# SCH_dock_2024-07-09.net
KiCad netlist of a schematic drawn in EasyEDA
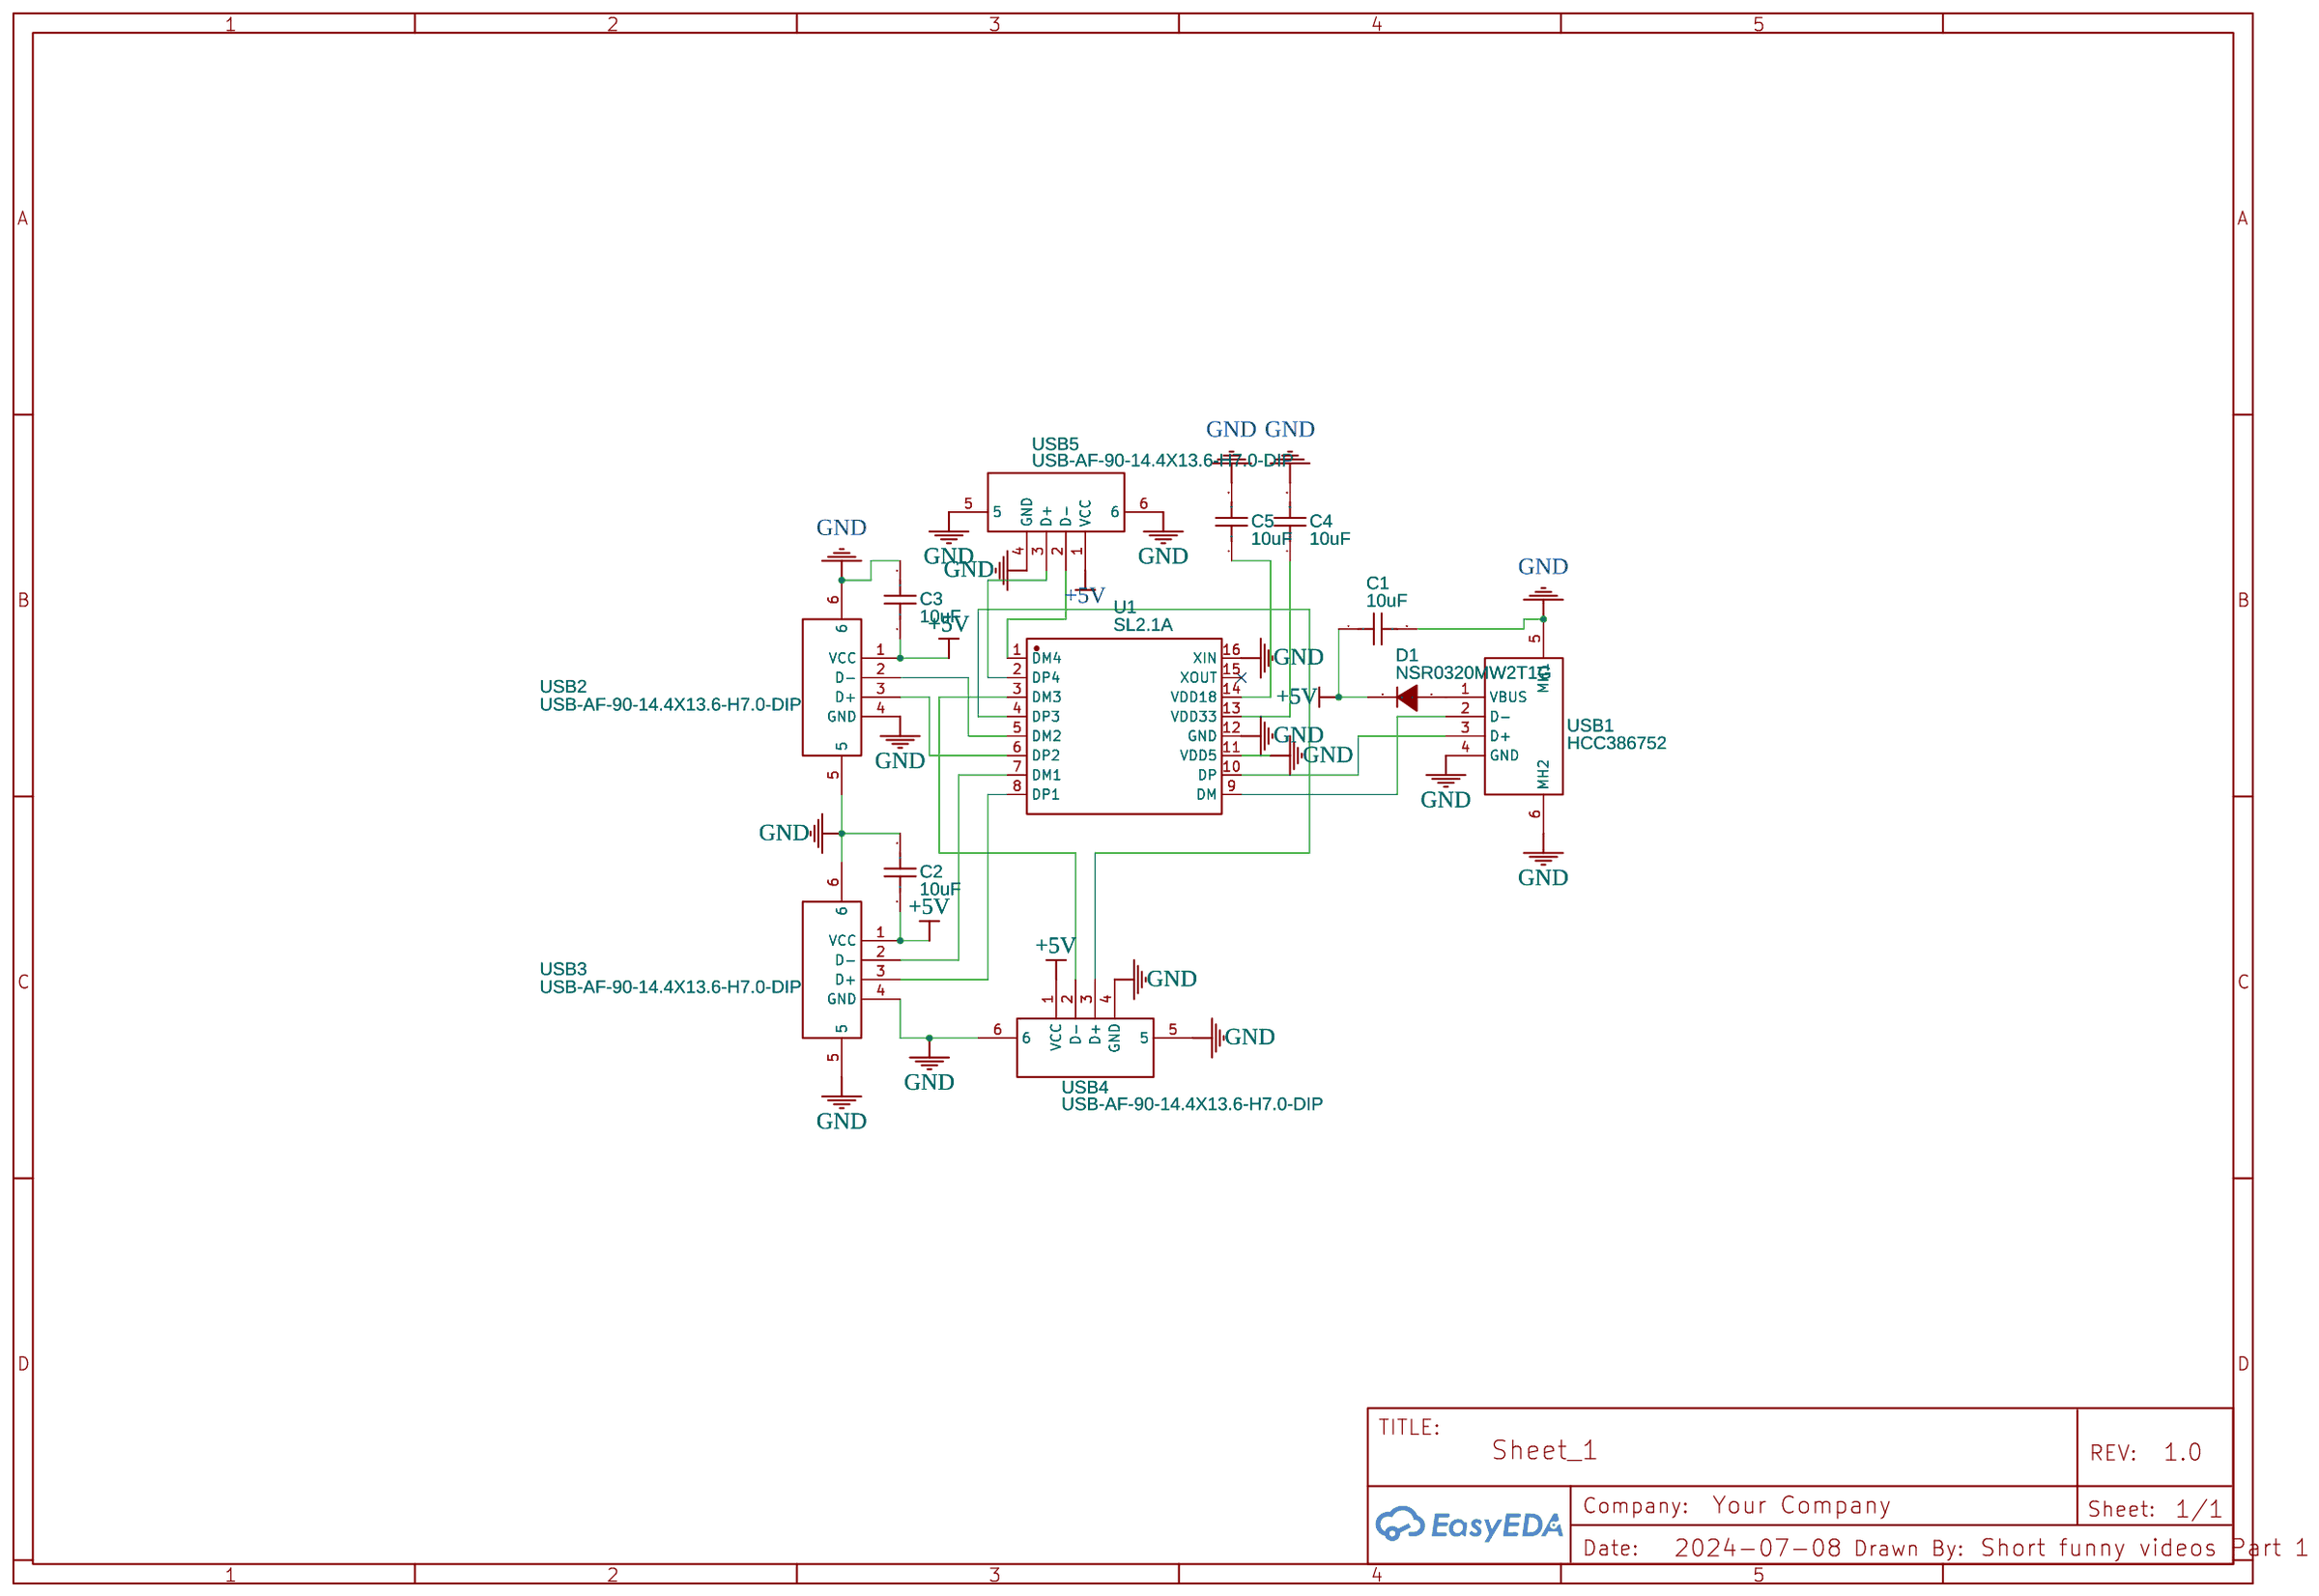
[diagram p0: schematic sheet]

(export (version "E")
  (design (tool "Eeschema 10.0.6"))
  (components
    (comp (ref "C1")
      (value "10uF")
      (fields
        (field (name "Manufacturer Part") "CL10A106KP8NNNC")
        (field (name "Manufacturer") "SAMSUNG(三星)")
      )
      (libsource (lib "") (part "CL10A106KP8NNNC_2"))
    )
    (comp (ref "C2")
      (value "10uF")
      (fields
        (field (name "Manufacturer Part") "CL10A106KP8NNNC")
        (field (name "Manufacturer") "SAMSUNG(三星)")
      )
      (libsource (lib "") (part "CL10A106KP8NNNC_1"))
    )
    (comp (ref "C3")
      (value "10uF")
      (fields
        (field (name "Manufacturer Part") "CL10A106KP8NNNC")
        (field (name "Manufacturer") "SAMSUNG(三星)")
      )
      (libsource (lib "") (part "CL10A106KP8NNNC"))
    )
    (comp (ref "C4")
      (value "10uF")
      (fields
        (field (name "Manufacturer Part") "CL10A106KP8NNNC")
        (field (name "Manufacturer") "SAMSUNG(三星)")
      )
      (libsource (lib "") (part "CL10A106KP8NNNC"))
    )
    (comp (ref "C5")
      (value "10uF")
      (fields
        (field (name "Manufacturer Part") "CL10A106KP8NNNC")
        (field (name "Manufacturer") "SAMSUNG(三星)")
      )
      (libsource (lib "") (part "CL10A106KP8NNNC"))
    )
    (comp (ref "D1")
      (value "NSR0320MW2T1G")
      (fields (field (name "Manufacturer") "onsemi(安森美)"))
      (libsource (lib "") (part "NSR0320MW2T1G"))
    )
    (comp (ref "U1")
      (value "SL2.1A")
      (fields (field (name "Manufacturer") "CoreChips(和芯润德)"))
      (libsource (lib "") (part "SL2.1A"))
    )
    (comp (ref "USB1")
      (value "HCC386752")
      (fields (field (name "Manufacturer Part") "U-USBAR04P-M003") (field (name "Manufacturer") "Ckmtw(灿科盟)"))
      (libsource (lib "") (part "HCC386752"))
    )
    (comp (ref "USB2")
      (value "USB-AF-90-14.4X13.6-H7.0-DIP")
      (fields (field (name "Manufacturer Part") "903-131A1011D10100") (field (name "Manufacturer") "精拓金"))
      (libsource (lib "") (part "USB-AF-90-14.4X13.6-H7.0-DIP"))
    )
    (comp (ref "USB3")
      (value "USB-AF-90-14.4X13.6-H7.0-DIP")
      (fields (field (name "Manufacturer Part") "903-131A1011D10100") (field (name "Manufacturer") "精拓金"))
      (libsource (lib "") (part "USB-AF-90-14.4X13.6-H7.0-DIP"))
    )
    (comp (ref "USB4")
      (value "USB-AF-90-14.4X13.6-H7.0-DIP")
      (fields (field (name "Manufacturer Part") "903-131A1011D10100") (field (name "Manufacturer") "精拓金"))
      (libsource (lib "") (part "USB-AF-90-14.4X13.6-H7.0-DIP_2"))
    )
    (comp (ref "USB5")
      (value "USB-AF-90-14.4X13.6-H7.0-DIP")
      (fields (field (name "Manufacturer Part") "903-131A1011D10100") (field (name "Manufacturer") "精拓金"))
      (libsource (lib "") (part "USB-AF-90-14.4X13.6-H7.0-DIP_1"))
    )
  )
  (nets
    (net (code "1") (name "+5V") (class "Default")
      (node (ref "C1") (pin "1") (pinfunction "1_1") (pintype "unspecified"))
      (node (ref "C2") (pin "2") (pinfunction "2_2") (pintype "unspecified"))
      (node (ref "C3") (pin "1") (pinfunction "1_1") (pintype "unspecified"))
      (node (ref "D1") (pin "1") (pinfunction "C_1") (pintype "unspecified"))
      (node (ref "USB2") (pin "1") (pinfunction "VCC_1") (pintype "unspecified"))
      (node (ref "USB3") (pin "1") (pinfunction "VCC_1") (pintype "unspecified"))
      (node (ref "USB4") (pin "1") (pinfunction "VCC_1") (pintype "unspecified"))
      (node (ref "USB5") (pin "1") (pinfunction "VCC_1") (pintype "unspecified"))
    )
    (net (code "2") (name "GND") (class "Default")
      (node (ref "C1") (pin "2") (pinfunction "2_2") (pintype "unspecified"))
      (node (ref "C2") (pin "1") (pinfunction "1_1") (pintype "unspecified"))
      (node (ref "C3") (pin "2") (pinfunction "2_2") (pintype "unspecified"))
      (node (ref "C4") (pin "2") (pinfunction "2_2") (pintype "unspecified"))
      (node (ref "C5") (pin "2") (pinfunction "2_2") (pintype "unspecified"))
      (node (ref "U1") (pin "11") (pinfunction "VDD5_11") (pintype "unspecified"))
      (node (ref "U1") (pin "12") (pinfunction "GND_12") (pintype "unspecified"))
      (node (ref "U1") (pin "16") (pinfunction "XIN_16") (pintype "unspecified"))
      (node (ref "USB1") (pin "4") (pinfunction "GND_4") (pintype "unspecified"))
      (node (ref "USB1") (pin "5") (pinfunction "MH1_5") (pintype "unspecified"))
      (node (ref "USB1") (pin "6") (pinfunction "MH2_6") (pintype "unspecified"))
      (node (ref "USB2") (pin "4") (pinfunction "GND_4") (pintype "unspecified"))
      (node (ref "USB2") (pin "5") (pinfunction "5_5") (pintype "unspecified"))
      (node (ref "USB2") (pin "6") (pinfunction "6_6") (pintype "unspecified"))
      (node (ref "USB3") (pin "4") (pinfunction "GND_4") (pintype "unspecified"))
      (node (ref "USB3") (pin "5") (pinfunction "5_5") (pintype "unspecified"))
      (node (ref "USB3") (pin "6") (pinfunction "6_6") (pintype "unspecified"))
      (node (ref "USB4") (pin "4") (pinfunction "GND_4") (pintype "unspecified"))
      (node (ref "USB4") (pin "5") (pinfunction "5_5") (pintype "unspecified"))
      (node (ref "USB4") (pin "6") (pinfunction "6_6") (pintype "unspecified"))
      (node (ref "USB5") (pin "4") (pinfunction "GND_4") (pintype "unspecified"))
      (node (ref "USB5") (pin "5") (pinfunction "5_5") (pintype "unspecified"))
      (node (ref "USB5") (pin "6") (pinfunction "6_6") (pintype "unspecified"))
    )
    (net (code "3") (name "Net-(D1-A)") (class "Default")
      (node (ref "D1") (pin "2") (pinfunction "A_2") (pintype "unspecified"))
      (node (ref "USB1") (pin "1") (pinfunction "VBUS_1") (pintype "unspecified"))
    )
    (net (code "4") (name "Net-(U1-DM)") (class "Default")
      (node (ref "U1") (pin "9") (pinfunction "DM_9") (pintype "unspecified"))
      (node (ref "USB1") (pin "2") (pinfunction "D-_2") (pintype "unspecified"))
    )
    (net (code "5") (name "Net-(U1-DM1)") (class "Default")
      (node (ref "U1") (pin "7") (pinfunction "DM1_7") (pintype "unspecified"))
      (node (ref "USB3") (pin "2") (pinfunction "D-_2") (pintype "unspecified"))
    )
    (net (code "6") (name "Net-(U1-DM2)") (class "Default")
      (node (ref "U1") (pin "5") (pinfunction "DM2_5") (pintype "unspecified"))
      (node (ref "USB2") (pin "2") (pinfunction "D-_2") (pintype "unspecified"))
    )
    (net (code "7") (name "Net-(U1-DM3)") (class "Default")
      (node (ref "U1") (pin "3") (pinfunction "DM3_3") (pintype "unspecified"))
      (node (ref "USB4") (pin "2") (pinfunction "D-_2") (pintype "unspecified"))
    )
    (net (code "8") (name "Net-(U1-DM4)") (class "Default")
      (node (ref "U1") (pin "1") (pinfunction "DM4_1") (pintype "unspecified"))
      (node (ref "USB5") (pin "2") (pinfunction "D-_2") (pintype "unspecified"))
    )
    (net (code "9") (name "Net-(U1-DP)") (class "Default")
      (node (ref "U1") (pin "10") (pinfunction "DP_10") (pintype "unspecified"))
      (node (ref "USB1") (pin "3") (pinfunction "D+_3") (pintype "unspecified"))
    )
    (net (code "10") (name "Net-(U1-DP1)") (class "Default")
      (node (ref "U1") (pin "8") (pinfunction "DP1_8") (pintype "unspecified"))
      (node (ref "USB3") (pin "3") (pinfunction "D+_3") (pintype "unspecified"))
    )
    (net (code "11") (name "Net-(U1-DP2)") (class "Default")
      (node (ref "U1") (pin "6") (pinfunction "DP2_6") (pintype "unspecified"))
      (node (ref "USB2") (pin "3") (pinfunction "D+_3") (pintype "unspecified"))
    )
    (net (code "12") (name "Net-(U1-DP3)") (class "Default")
      (node (ref "U1") (pin "4") (pinfunction "DP3_4") (pintype "unspecified"))
      (node (ref "USB4") (pin "3") (pinfunction "D+_3") (pintype "unspecified"))
    )
    (net (code "13") (name "Net-(U1-DP4)") (class "Default")
      (node (ref "U1") (pin "2") (pinfunction "DP4_2") (pintype "unspecified"))
      (node (ref "USB5") (pin "3") (pinfunction "D+_3") (pintype "unspecified"))
    )
    (net (code "14") (name "Net-(U1-VDD18)") (class "Default")
      (node (ref "C5") (pin "1") (pinfunction "1_1") (pintype "unspecified"))
      (node (ref "U1") (pin "14") (pinfunction "VDD18_14") (pintype "unspecified"))
    )
    (net (code "15") (name "Net-(U1-VDD33)") (class "Default")
      (node (ref "C4") (pin "1") (pinfunction "1_1") (pintype "unspecified"))
      (node (ref "U1") (pin "13") (pinfunction "VDD33_13") (pintype "unspecified"))
    )
    (net (code "16") (name "unconnected-(U1-XOUT-Pad15)") (class "Default")
      (node (ref "U1") (pin "15") (pinfunction "XOUT_15") (pintype "unspecified+no_connect"))
    )
  )
)
